# control_v1.net
KiCad netlist of a schematic drawn in EAGLE
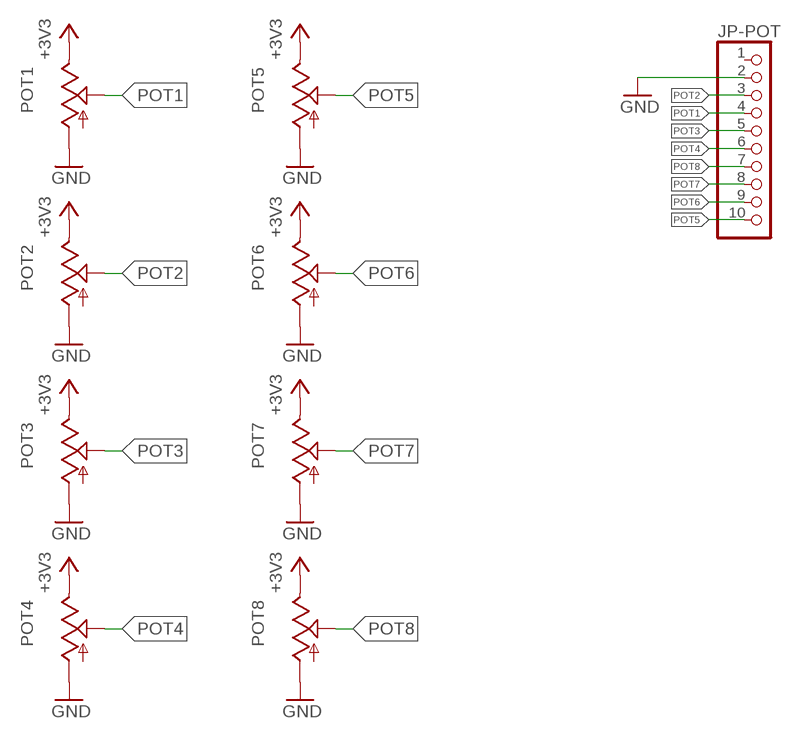
[diagram p0: schematic, sheet 1]
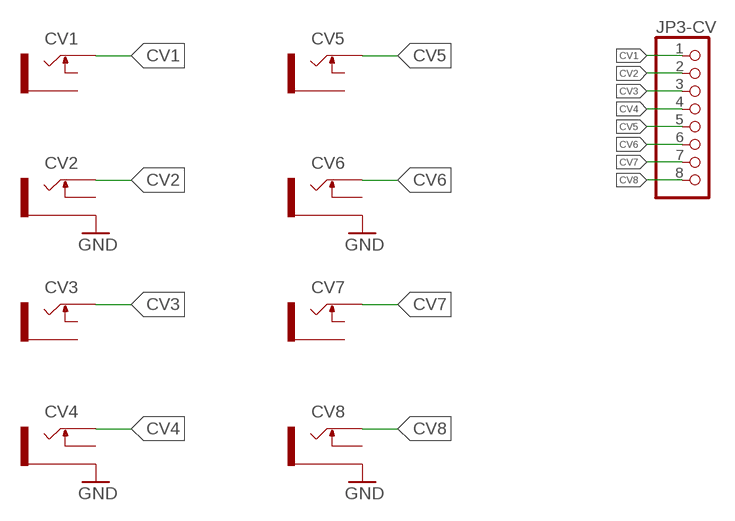
[diagram p1: schematic, sheet 2]
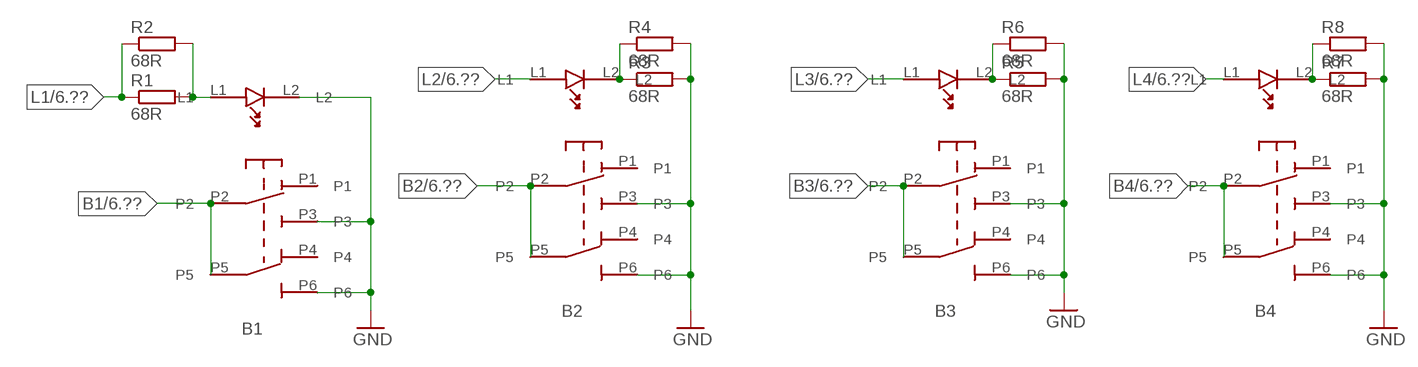
[diagram p2: schematic, sheet 3]
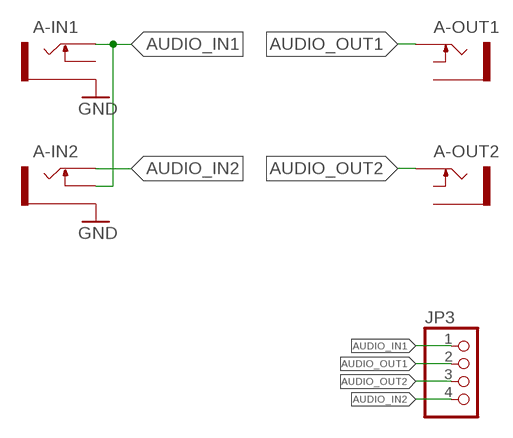
[diagram p3: schematic, sheet 4]
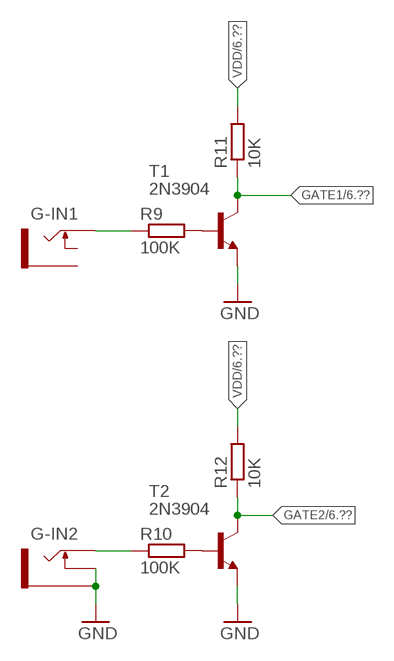
[diagram p4: schematic, sheet 5]
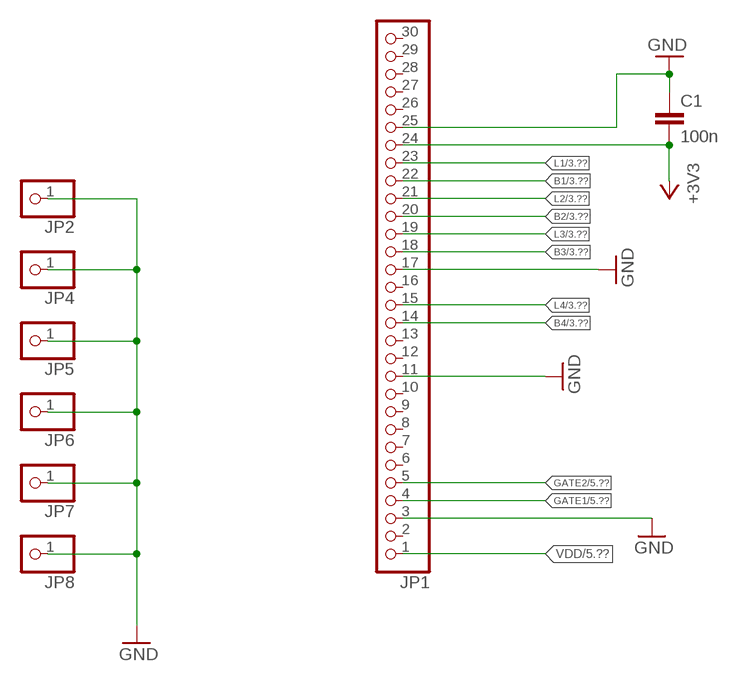
[diagram p5: schematic, sheet 6]

(export (version "E")
  (design (tool "Eeschema 10.0.6"))
  (components
    (comp (ref "JP-POT")
      (value "PINHD-1X10_2.54")
      (footprint "eagle-import:1X10")
      (libsource (lib "eagle-import") (part "PINHD-1X10_2.54"))
    )
    (comp (ref "POT1")
      (value "9MM_SNAP-IN_POT_")
      (footprint "eagle-import:9MM_SNAP-IN_POT")
      (libsource (lib "eagle-import") (part "9MM_SNAP-IN_POT_"))
    )
    (comp (ref "POT2")
      (value "9MM_SNAP-IN_POT_")
      (footprint "eagle-import:9MM_SNAP-IN_POT")
      (libsource (lib "eagle-import") (part "9MM_SNAP-IN_POT_"))
    )
    (comp (ref "POT3")
      (value "9MM_SNAP-IN_POT_")
      (footprint "eagle-import:9MM_SNAP-IN_POT")
      (libsource (lib "eagle-import") (part "9MM_SNAP-IN_POT_"))
    )
    (comp (ref "POT4")
      (value "9MM_SNAP-IN_POT_")
      (footprint "eagle-import:9MM_SNAP-IN_POT")
      (libsource (lib "eagle-import") (part "9MM_SNAP-IN_POT_"))
    )
    (comp (ref "POT5")
      (value "9MM_SNAP-IN_POT_")
      (footprint "eagle-import:9MM_SNAP-IN_POT")
      (libsource (lib "eagle-import") (part "9MM_SNAP-IN_POT_"))
    )
    (comp (ref "POT6")
      (value "9MM_SNAP-IN_POT_")
      (footprint "eagle-import:9MM_SNAP-IN_POT")
      (libsource (lib "eagle-import") (part "9MM_SNAP-IN_POT_"))
    )
    (comp (ref "POT7")
      (value "9MM_SNAP-IN_POT_")
      (footprint "eagle-import:9MM_SNAP-IN_POT")
      (libsource (lib "eagle-import") (part "9MM_SNAP-IN_POT_"))
    )
    (comp (ref "POT8")
      (value "9MM_SNAP-IN_POT_")
      (footprint "eagle-import:9MM_SNAP-IN_POT")
      (libsource (lib "eagle-import") (part "9MM_SNAP-IN_POT_"))
    )
    (comp (ref "C1")
      (value "100n")
      (footprint "eagle-import:C025-025X050")
      (libsource (lib "eagle-import") (part "C-EU025-025X050"))
    )
    (comp (ref "JP1")
      (value "PINHD-1X30")
      (footprint "eagle-import:1X30")
      (libsource (lib "eagle-import") (part "PINHD-1X30"))
    )
    (comp (ref "JP2")
      (value "PINHD-1X1")
      (footprint "eagle-import:1X01")
      (libsource (lib "eagle-import") (part "PINHD-1X1"))
    )
    (comp (ref "JP4")
      (value "PINHD-1X1")
      (footprint "eagle-import:1X01")
      (libsource (lib "eagle-import") (part "PINHD-1X1"))
    )
    (comp (ref "JP5")
      (value "PINHD-1X1")
      (footprint "eagle-import:1X01")
      (libsource (lib "eagle-import") (part "PINHD-1X1"))
    )
    (comp (ref "JP6")
      (value "PINHD-1X1")
      (footprint "eagle-import:1X01")
      (libsource (lib "eagle-import") (part "PINHD-1X1"))
    )
    (comp (ref "JP7")
      (value "PINHD-1X1")
      (footprint "eagle-import:1X01")
      (libsource (lib "eagle-import") (part "PINHD-1X1"))
    )
    (comp (ref "JP8")
      (value "PINHD-1X1")
      (footprint "eagle-import:1X01")
      (libsource (lib "eagle-import") (part "PINHD-1X1"))
    )
    (comp (ref "G-IN1")
      (value "THONKICONNNEW")
      (footprint "eagle-import:WQP-PJ301M-12_JACK")
      (libsource (lib "eagle-import") (part "MusicThingModular mod_THONKICONNNEW"))
    )
    (comp (ref "G-IN2")
      (value "THONKICONNNEW")
      (footprint "eagle-import:WQP-PJ301M-12_JACK")
      (libsource (lib "eagle-import") (part "THONKICONNNEW"))
    )
    (comp (ref "R9")
      (value "100K")
      (footprint "eagle-import:0207_7")
      (libsource (lib "eagle-import") (part "R-EU_0207/7"))
    )
    (comp (ref "R10")
      (value "100K")
      (footprint "eagle-import:0207_7")
      (libsource (lib "eagle-import") (part "R-EU_0207/7"))
    )
    (comp (ref "R11")
      (value "10K")
      (footprint "eagle-import:0207_7")
      (libsource (lib "eagle-import") (part "R-EU_0207/7"))
    )
    (comp (ref "R12")
      (value "10K")
      (footprint "eagle-import:0207_7")
      (libsource (lib "eagle-import") (part "R-EU_0207/7"))
    )
    (comp (ref "T1")
      (value "2N3904")
      (footprint "eagle-import:TO92")
      (libsource (lib "eagle-import") (part "2N3904"))
    )
    (comp (ref "T2")
      (value "2N3904")
      (footprint "eagle-import:TO92")
      (libsource (lib "eagle-import") (part "2N3904"))
    )
    (comp (ref "B1")
      (value "LP4OA1PBCTG")
      (footprint "eagle-import:LP4OA1PBCT")
      (libsource (lib "eagle-import") (part "LP4OA1PBCTG"))
    )
    (comp (ref "B2")
      (value "LP4OA1PBCTG")
      (footprint "eagle-import:LP4OA1PBCT")
      (libsource (lib "eagle-import") (part "LP4OA1PBCTG"))
    )
    (comp (ref "B3")
      (value "LP4OA1PBCTG")
      (footprint "eagle-import:LP4OA1PBCT")
      (libsource (lib "eagle-import") (part "LP4OA1PBCTG"))
    )
    (comp (ref "B4")
      (value "LP4OA1PBCTG")
      (footprint "eagle-import:LP4OA1PBCT")
      (libsource (lib "eagle-import") (part "LP4OA1PBCTG"))
    )
    (comp (ref "R1")
      (value "68R")
      (footprint "eagle-import:0207_7")
      (libsource (lib "eagle-import") (part "R-EU_0207/7"))
    )
    (comp (ref "R2")
      (value "68R")
      (footprint "eagle-import:0207_7")
      (libsource (lib "eagle-import") (part "R-EU_0207/7"))
    )
    (comp (ref "R3")
      (value "68R")
      (footprint "eagle-import:0207_7")
      (libsource (lib "eagle-import") (part "R-EU_0207/7"))
    )
    (comp (ref "R4")
      (value "68R")
      (footprint "eagle-import:0207_7")
      (libsource (lib "eagle-import") (part "R-EU_0207/7"))
    )
    (comp (ref "R5")
      (value "68R")
      (footprint "eagle-import:0207_7")
      (libsource (lib "eagle-import") (part "R-EU_0207/7"))
    )
    (comp (ref "R6")
      (value "68R")
      (footprint "eagle-import:0207_7")
      (libsource (lib "eagle-import") (part "R-EU_0207/7"))
    )
    (comp (ref "R7")
      (value "68R")
      (footprint "eagle-import:0207_7")
      (libsource (lib "eagle-import") (part "R-EU_0207/7"))
    )
    (comp (ref "R8")
      (value "68R")
      (footprint "eagle-import:0207_7")
      (libsource (lib "eagle-import") (part "R-EU_0207/7"))
    )
    (comp (ref "CV1")
      (value "THONKICONNNEW")
      (footprint "eagle-import:WQP-PJ301M-12_JACK")
      (libsource (lib "eagle-import") (part "MusicThingModular mod_THONKICONNNEW"))
    )
    (comp (ref "CV2")
      (value "THONKICONNNEW")
      (footprint "eagle-import:WQP-PJ301M-12_JACK")
      (libsource (lib "eagle-import") (part "THONKICONNNEW"))
    )
    (comp (ref "CV3")
      (value "THONKICONNNEW")
      (footprint "eagle-import:WQP-PJ301M-12_JACK")
      (libsource (lib "eagle-import") (part "MusicThingModular mod_THONKICONNNEW"))
    )
    (comp (ref "CV4")
      (value "THONKICONNNEW")
      (footprint "eagle-import:WQP-PJ301M-12_JACK")
      (libsource (lib "eagle-import") (part "THONKICONNNEW"))
    )
    (comp (ref "CV5")
      (value "THONKICONNNEW")
      (footprint "eagle-import:WQP-PJ301M-12_JACK")
      (libsource (lib "eagle-import") (part "MusicThingModular mod_THONKICONNNEW"))
    )
    (comp (ref "CV6")
      (value "THONKICONNNEW")
      (footprint "eagle-import:WQP-PJ301M-12_JACK")
      (libsource (lib "eagle-import") (part "THONKICONNNEW"))
    )
    (comp (ref "CV7")
      (value "THONKICONNNEW")
      (footprint "eagle-import:WQP-PJ301M-12_JACK")
      (libsource (lib "eagle-import") (part "MusicThingModular mod_THONKICONNNEW"))
    )
    (comp (ref "CV8")
      (value "THONKICONNNEW")
      (footprint "eagle-import:WQP-PJ301M-12_JACK")
      (libsource (lib "eagle-import") (part "THONKICONNNEW"))
    )
    (comp (ref "JP3-CV")
      (value "PINHD-1X8")
      (footprint "eagle-import:1X08")
      (libsource (lib "eagle-import") (part "PINHD-1X8"))
    )
    (comp (ref "A-IN1")
      (value "THONKICONNNEW")
      (footprint "eagle-import:WQP-PJ301M-12_JACK")
      (libsource (lib "eagle-import") (part "THONKICONNNEW"))
    )
    (comp (ref "A-IN2")
      (value "THONKICONNNEW")
      (footprint "eagle-import:WQP-PJ301M-12_JACK")
      (libsource (lib "eagle-import") (part "THONKICONNNEW"))
    )
    (comp (ref "A-OUT1")
      (value "THONKICONNNEW")
      (footprint "eagle-import:WQP-PJ301M-12_JACK")
      (libsource (lib "eagle-import") (part "MusicThingModular mod_THONKICONNNEW"))
    )
    (comp (ref "A-OUT2")
      (value "THONKICONNNEW")
      (footprint "eagle-import:WQP-PJ301M-12_JACK")
      (libsource (lib "eagle-import") (part "MusicThingModular mod_THONKICONNNEW"))
    )
    (comp (ref "JP3")
      (value "PINHD-1X4")
      (footprint "eagle-import:1X04")
      (libsource (lib "eagle-import") (part "PINHD-1X4"))
    )
  )
  (nets
    (net (code "1") (name "+3V3") (class "Default")
      (node (ref "C1") (pin "2") (pinfunction "2_2") (pintype "passive"))
      (node (ref "JP1") (pin "24") (pinfunction "24_24") (pintype "passive"))
      (node (ref "POT1") (pin "3") (pinfunction "E_3") (pintype "passive"))
      (node (ref "POT2") (pin "3") (pinfunction "E_3") (pintype "passive"))
      (node (ref "POT3") (pin "3") (pinfunction "E_3") (pintype "passive"))
      (node (ref "POT4") (pin "3") (pinfunction "E_3") (pintype "passive"))
      (node (ref "POT5") (pin "3") (pinfunction "E_3") (pintype "passive"))
      (node (ref "POT6") (pin "3") (pinfunction "E_3") (pintype "passive"))
      (node (ref "POT7") (pin "3") (pinfunction "E_3") (pintype "passive"))
      (node (ref "POT8") (pin "3") (pinfunction "E_3") (pintype "passive"))
    )
    (net (code "2") (name "AUDIO_IN1") (class "Default")
      (node (ref "A-IN1") (pin "P$1_TIP") (pinfunction "TIP_P$1_TIP") (pintype "passive"))
      (node (ref "A-IN2") (pin "P$2_SWITCH") (pinfunction "SWITCH_P$2_SWITCH") (pintype "passive"))
      (node (ref "JP3") (pin "1") (pinfunction "1_1") (pintype "passive"))
    )
    (net (code "3") (name "AUDIO_IN2") (class "Default")
      (node (ref "A-IN2") (pin "P$1_TIP") (pinfunction "TIP_P$1_TIP") (pintype "passive"))
      (node (ref "JP3") (pin "4") (pinfunction "4_4") (pintype "passive"))
    )
    (net (code "4") (name "AUDIO_OUT1") (class "Default")
      (node (ref "A-OUT1") (pin "P$1_TIP") (pinfunction "TIP_P$1_TIP") (pintype "passive"))
      (node (ref "JP3") (pin "2") (pinfunction "2_2") (pintype "passive"))
    )
    (net (code "5") (name "AUDIO_OUT2") (class "Default")
      (node (ref "A-OUT2") (pin "P$1_TIP") (pinfunction "TIP_P$1_TIP") (pintype "passive"))
      (node (ref "JP3") (pin "3") (pinfunction "3_3") (pintype "passive"))
    )
    (net (code "6") (name "B1") (class "Default")
      (node (ref "B1") (pin "P2") (pinfunction "P2_P2") (pintype "bidirectional"))
      (node (ref "B1") (pin "P5") (pinfunction "P5_P5") (pintype "bidirectional"))
      (node (ref "JP1") (pin "22") (pinfunction "22_22") (pintype "passive"))
    )
    (net (code "7") (name "B2") (class "Default")
      (node (ref "B2") (pin "P2") (pinfunction "P2_P2") (pintype "bidirectional"))
      (node (ref "B2") (pin "P5") (pinfunction "P5_P5") (pintype "bidirectional"))
      (node (ref "JP1") (pin "20") (pinfunction "20_20") (pintype "passive"))
    )
    (net (code "8") (name "B3") (class "Default")
      (node (ref "B3") (pin "P2") (pinfunction "P2_P2") (pintype "bidirectional"))
      (node (ref "B3") (pin "P5") (pinfunction "P5_P5") (pintype "bidirectional"))
      (node (ref "JP1") (pin "18") (pinfunction "18_18") (pintype "passive"))
    )
    (net (code "9") (name "B4") (class "Default")
      (node (ref "B4") (pin "P2") (pinfunction "P2_P2") (pintype "bidirectional"))
      (node (ref "B4") (pin "P5") (pinfunction "P5_P5") (pintype "bidirectional"))
      (node (ref "JP1") (pin "14") (pinfunction "14_14") (pintype "passive"))
    )
    (net (code "10") (name "CV1") (class "Default")
      (node (ref "CV1") (pin "P$1_TIP") (pinfunction "TIP_P$1_TIP") (pintype "passive"))
      (node (ref "JP3-CV") (pin "1") (pinfunction "1_1") (pintype "passive"))
    )
    (net (code "11") (name "CV2") (class "Default")
      (node (ref "CV2") (pin "P$1_TIP") (pinfunction "TIP_P$1_TIP") (pintype "passive"))
      (node (ref "JP3-CV") (pin "2") (pinfunction "2_2") (pintype "passive"))
    )
    (net (code "12") (name "CV3") (class "Default")
      (node (ref "CV3") (pin "P$1_TIP") (pinfunction "TIP_P$1_TIP") (pintype "passive"))
      (node (ref "JP3-CV") (pin "3") (pinfunction "3_3") (pintype "passive"))
    )
    (net (code "13") (name "CV4") (class "Default")
      (node (ref "CV4") (pin "P$1_TIP") (pinfunction "TIP_P$1_TIP") (pintype "passive"))
      (node (ref "JP3-CV") (pin "4") (pinfunction "4_4") (pintype "passive"))
    )
    (net (code "14") (name "CV5") (class "Default")
      (node (ref "CV5") (pin "P$1_TIP") (pinfunction "TIP_P$1_TIP") (pintype "passive"))
      (node (ref "JP3-CV") (pin "5") (pinfunction "5_5") (pintype "passive"))
    )
    (net (code "15") (name "CV6") (class "Default")
      (node (ref "CV6") (pin "P$1_TIP") (pinfunction "TIP_P$1_TIP") (pintype "passive"))
      (node (ref "JP3-CV") (pin "6") (pinfunction "6_6") (pintype "passive"))
    )
    (net (code "16") (name "CV7") (class "Default")
      (node (ref "CV7") (pin "P$1_TIP") (pinfunction "TIP_P$1_TIP") (pintype "passive"))
      (node (ref "JP3-CV") (pin "7") (pinfunction "7_7") (pintype "passive"))
    )
    (net (code "17") (name "CV8") (class "Default")
      (node (ref "CV8") (pin "P$1_TIP") (pinfunction "TIP_P$1_TIP") (pintype "passive"))
      (node (ref "JP3-CV") (pin "8") (pinfunction "8_8") (pintype "passive"))
    )
    (net (code "18") (name "GATE1") (class "Default")
      (node (ref "JP1") (pin "4") (pinfunction "4_4") (pintype "passive"))
      (node (ref "R11") (pin "1") (pinfunction "1_1") (pintype "passive"))
      (node (ref "T1") (pin "1") (pinfunction "C_1") (pintype "passive"))
    )
    (net (code "19") (name "GATE2") (class "Default")
      (node (ref "JP1") (pin "5") (pinfunction "5_5") (pintype "passive"))
      (node (ref "R12") (pin "1") (pinfunction "1_1") (pintype "passive"))
      (node (ref "T2") (pin "1") (pinfunction "C_1") (pintype "passive"))
    )
    (net (code "20") (name "GND") (class "Default")
      (node (ref "A-IN1") (pin "P$3_SLEEVE") (pinfunction "SLEEVE_P$3_SLEEVE") (pintype "passive"))
      (node (ref "A-IN2") (pin "P$3_SLEEVE") (pinfunction "SLEEVE_P$3_SLEEVE") (pintype "passive"))
      (node (ref "B1") (pin "L2") (pinfunction "L2_L2") (pintype "output"))
      (node (ref "B1") (pin "P3") (pinfunction "P3_P3") (pintype "bidirectional"))
      (node (ref "B1") (pin "P6") (pinfunction "P6_P6") (pintype "bidirectional"))
      (node (ref "B2") (pin "P3") (pinfunction "P3_P3") (pintype "bidirectional"))
      (node (ref "B2") (pin "P6") (pinfunction "P6_P6") (pintype "bidirectional"))
      (node (ref "B3") (pin "P3") (pinfunction "P3_P3") (pintype "bidirectional"))
      (node (ref "B3") (pin "P6") (pinfunction "P6_P6") (pintype "bidirectional"))
      (node (ref "B4") (pin "P3") (pinfunction "P3_P3") (pintype "bidirectional"))
      (node (ref "B4") (pin "P6") (pinfunction "P6_P6") (pintype "bidirectional"))
      (node (ref "C1") (pin "1") (pinfunction "1_1") (pintype "passive"))
      (node (ref "CV2") (pin "P$3_SLEEVE") (pinfunction "SLEEVE_P$3_SLEEVE") (pintype "passive"))
      (node (ref "CV4") (pin "P$3_SLEEVE") (pinfunction "SLEEVE_P$3_SLEEVE") (pintype "passive"))
      (node (ref "CV6") (pin "P$3_SLEEVE") (pinfunction "SLEEVE_P$3_SLEEVE") (pintype "passive"))
      (node (ref "CV8") (pin "P$3_SLEEVE") (pinfunction "SLEEVE_P$3_SLEEVE") (pintype "passive"))
      (node (ref "G-IN2") (pin "P$2_SWITCH") (pinfunction "SWITCH_P$2_SWITCH") (pintype "passive"))
      (node (ref "G-IN2") (pin "P$3_SLEEVE") (pinfunction "SLEEVE_P$3_SLEEVE") (pintype "passive"))
      (node (ref "JP-POT") (pin "2") (pinfunction "2_2") (pintype "passive"))
      (node (ref "JP1") (pin "11") (pinfunction "11_11") (pintype "passive"))
      (node (ref "JP1") (pin "17") (pinfunction "17_17") (pintype "passive"))
      (node (ref "JP1") (pin "25") (pinfunction "25_25") (pintype "passive"))
      (node (ref "JP1") (pin "3") (pinfunction "3_3") (pintype "passive"))
      (node (ref "JP2") (pin "1") (pinfunction "1_1") (pintype "passive"))
      (node (ref "JP4") (pin "1") (pinfunction "1_1") (pintype "passive"))
      (node (ref "JP5") (pin "1") (pinfunction "1_1") (pintype "passive"))
      (node (ref "JP6") (pin "1") (pinfunction "1_1") (pintype "passive"))
      (node (ref "JP7") (pin "1") (pinfunction "1_1") (pintype "passive"))
      (node (ref "JP8") (pin "1") (pinfunction "1_1") (pintype "passive"))
      (node (ref "POT1") (pin "1") (pinfunction "A_1") (pintype "passive"))
      (node (ref "POT2") (pin "1") (pinfunction "A_1") (pintype "passive"))
      (node (ref "POT3") (pin "1") (pinfunction "A_1") (pintype "passive"))
      (node (ref "POT4") (pin "1") (pinfunction "A_1") (pintype "passive"))
      (node (ref "POT5") (pin "1") (pinfunction "A_1") (pintype "passive"))
      (node (ref "POT6") (pin "1") (pinfunction "A_1") (pintype "passive"))
      (node (ref "POT7") (pin "1") (pinfunction "A_1") (pintype "passive"))
      (node (ref "POT8") (pin "1") (pinfunction "A_1") (pintype "passive"))
      (node (ref "R3") (pin "2") (pinfunction "2_2") (pintype "passive"))
      (node (ref "R4") (pin "2") (pinfunction "2_2") (pintype "passive"))
      (node (ref "R5") (pin "2") (pinfunction "2_2") (pintype "passive"))
      (node (ref "R6") (pin "2") (pinfunction "2_2") (pintype "passive"))
      (node (ref "R7") (pin "2") (pinfunction "2_2") (pintype "passive"))
      (node (ref "R8") (pin "2") (pinfunction "2_2") (pintype "passive"))
      (node (ref "T1") (pin "3") (pinfunction "E_3") (pintype "passive"))
      (node (ref "T2") (pin "3") (pinfunction "E_3") (pintype "passive"))
    )
    (net (code "21") (name "L1") (class "Default")
      (node (ref "JP1") (pin "23") (pinfunction "23_23") (pintype "passive"))
      (node (ref "R1") (pin "1") (pinfunction "1_1") (pintype "passive"))
      (node (ref "R2") (pin "1") (pinfunction "1_1") (pintype "passive"))
    )
    (net (code "22") (name "L2") (class "Default")
      (node (ref "B2") (pin "L1") (pinfunction "L1_L1") (pintype "input"))
      (node (ref "JP1") (pin "21") (pinfunction "21_21") (pintype "passive"))
    )
    (net (code "23") (name "L3") (class "Default")
      (node (ref "B3") (pin "L1") (pinfunction "L1_L1") (pintype "input"))
      (node (ref "JP1") (pin "19") (pinfunction "19_19") (pintype "passive"))
    )
    (net (code "24") (name "L4") (class "Default")
      (node (ref "B4") (pin "L1") (pinfunction "L1_L1") (pintype "input"))
      (node (ref "JP1") (pin "15") (pinfunction "15_15") (pintype "passive"))
    )
    (net (code "25") (name "Net-(B1-PadL1)") (class "Default")
      (node (ref "B1") (pin "L1") (pinfunction "L1_L1") (pintype "input"))
      (node (ref "R1") (pin "2") (pinfunction "2_2") (pintype "passive"))
      (node (ref "R2") (pin "2") (pinfunction "2_2") (pintype "passive"))
    )
    (net (code "26") (name "Net-(B2-PadL2)") (class "Default")
      (node (ref "B2") (pin "L2") (pinfunction "L2_L2") (pintype "output"))
      (node (ref "R3") (pin "1") (pinfunction "1_1") (pintype "passive"))
      (node (ref "R4") (pin "1") (pinfunction "1_1") (pintype "passive"))
    )
    (net (code "27") (name "Net-(B3-PadL2)") (class "Default")
      (node (ref "B3") (pin "L2") (pinfunction "L2_L2") (pintype "output"))
      (node (ref "R5") (pin "1") (pinfunction "1_1") (pintype "passive"))
      (node (ref "R6") (pin "1") (pinfunction "1_1") (pintype "passive"))
    )
    (net (code "28") (name "Net-(B4-PadL2)") (class "Default")
      (node (ref "B4") (pin "L2") (pinfunction "L2_L2") (pintype "output"))
      (node (ref "R7") (pin "1") (pinfunction "1_1") (pintype "passive"))
      (node (ref "R8") (pin "1") (pinfunction "1_1") (pintype "passive"))
    )
    (net (code "29") (name "Net-(G-IN1-TIP)") (class "Default")
      (node (ref "G-IN1") (pin "P$1_TIP") (pinfunction "TIP_P$1_TIP") (pintype "passive"))
      (node (ref "R9") (pin "1") (pinfunction "1_1") (pintype "passive"))
    )
    (net (code "30") (name "Net-(G-IN2-TIP)") (class "Default")
      (node (ref "G-IN2") (pin "P$1_TIP") (pinfunction "TIP_P$1_TIP") (pintype "passive"))
      (node (ref "R10") (pin "1") (pinfunction "1_1") (pintype "passive"))
    )
    (net (code "31") (name "Net-(T1-B)") (class "Default")
      (node (ref "R9") (pin "2") (pinfunction "2_2") (pintype "passive"))
      (node (ref "T1") (pin "2") (pinfunction "B_2") (pintype "passive"))
    )
    (net (code "32") (name "Net-(T2-B)") (class "Default")
      (node (ref "R10") (pin "2") (pinfunction "2_2") (pintype "passive"))
      (node (ref "T2") (pin "2") (pinfunction "B_2") (pintype "passive"))
    )
    (net (code "33") (name "POT1") (class "Default")
      (node (ref "JP-POT") (pin "4") (pinfunction "4_4") (pintype "passive"))
      (node (ref "POT1") (pin "2") (pinfunction "S_2") (pintype "passive"))
    )
    (net (code "34") (name "POT2") (class "Default")
      (node (ref "JP-POT") (pin "3") (pinfunction "3_3") (pintype "passive"))
      (node (ref "POT2") (pin "2") (pinfunction "S_2") (pintype "passive"))
    )
    (net (code "35") (name "POT3") (class "Default")
      (node (ref "JP-POT") (pin "5") (pinfunction "5_5") (pintype "passive"))
      (node (ref "POT3") (pin "2") (pinfunction "S_2") (pintype "passive"))
    )
    (net (code "36") (name "POT4") (class "Default")
      (node (ref "JP-POT") (pin "6") (pinfunction "6_6") (pintype "passive"))
      (node (ref "POT4") (pin "2") (pinfunction "S_2") (pintype "passive"))
    )
    (net (code "37") (name "POT5") (class "Default")
      (node (ref "JP-POT") (pin "10") (pinfunction "10_10") (pintype "passive"))
      (node (ref "POT5") (pin "2") (pinfunction "S_2") (pintype "passive"))
    )
    (net (code "38") (name "POT6") (class "Default")
      (node (ref "JP-POT") (pin "9") (pinfunction "9_9") (pintype "passive"))
      (node (ref "POT6") (pin "2") (pinfunction "S_2") (pintype "passive"))
    )
    (net (code "39") (name "POT7") (class "Default")
      (node (ref "JP-POT") (pin "8") (pinfunction "8_8") (pintype "passive"))
      (node (ref "POT7") (pin "2") (pinfunction "S_2") (pintype "passive"))
    )
    (net (code "40") (name "POT8") (class "Default")
      (node (ref "JP-POT") (pin "7") (pinfunction "7_7") (pintype "passive"))
      (node (ref "POT8") (pin "2") (pinfunction "S_2") (pintype "passive"))
    )
    (net (code "41") (name "VDD") (class "Default")
      (node (ref "JP1") (pin "1") (pinfunction "1_1") (pintype "passive"))
      (node (ref "R11") (pin "2") (pinfunction "2_2") (pintype "passive"))
      (node (ref "R12") (pin "2") (pinfunction "2_2") (pintype "passive"))
    )
    (net (code "42") (name "unconnected-(A-IN1-SWITCH-PadP$2_SWITCH)") (class "Default")
      (node (ref "A-IN1") (pin "P$2_SWITCH") (pinfunction "SWITCH_P$2_SWITCH") (pintype "passive"))
    )
    (net (code "43") (name "unconnected-(B1-PadP1)") (class "Default")
      (node (ref "B1") (pin "P1") (pinfunction "P1_P1") (pintype "bidirectional"))
    )
    (net (code "44") (name "unconnected-(B1-PadP4)") (class "Default")
      (node (ref "B1") (pin "P4") (pinfunction "P4_P4") (pintype "bidirectional"))
    )
    (net (code "45") (name "unconnected-(B2-PadP1)") (class "Default")
      (node (ref "B2") (pin "P1") (pinfunction "P1_P1") (pintype "bidirectional"))
    )
    (net (code "46") (name "unconnected-(B2-PadP4)") (class "Default")
      (node (ref "B2") (pin "P4") (pinfunction "P4_P4") (pintype "bidirectional"))
    )
    (net (code "47") (name "unconnected-(B3-PadP1)") (class "Default")
      (node (ref "B3") (pin "P1") (pinfunction "P1_P1") (pintype "bidirectional"))
    )
    (net (code "48") (name "unconnected-(B3-PadP4)") (class "Default")
      (node (ref "B3") (pin "P4") (pinfunction "P4_P4") (pintype "bidirectional"))
    )
    (net (code "49") (name "unconnected-(B4-PadP1)") (class "Default")
      (node (ref "B4") (pin "P1") (pinfunction "P1_P1") (pintype "bidirectional"))
    )
    (net (code "50") (name "unconnected-(B4-PadP4)") (class "Default")
      (node (ref "B4") (pin "P4") (pinfunction "P4_P4") (pintype "bidirectional"))
    )
    (net (code "51") (name "unconnected-(CV2-SWITCH-PadP$2_SWITCH)") (class "Default")
      (node (ref "CV2") (pin "P$2_SWITCH") (pinfunction "SWITCH_P$2_SWITCH") (pintype "passive"))
    )
    (net (code "52") (name "unconnected-(CV4-SWITCH-PadP$2_SWITCH)") (class "Default")
      (node (ref "CV4") (pin "P$2_SWITCH") (pinfunction "SWITCH_P$2_SWITCH") (pintype "passive"))
    )
    (net (code "53") (name "unconnected-(CV6-SWITCH-PadP$2_SWITCH)") (class "Default")
      (node (ref "CV6") (pin "P$2_SWITCH") (pinfunction "SWITCH_P$2_SWITCH") (pintype "passive"))
    )
    (net (code "54") (name "unconnected-(CV8-SWITCH-PadP$2_SWITCH)") (class "Default")
      (node (ref "CV8") (pin "P$2_SWITCH") (pinfunction "SWITCH_P$2_SWITCH") (pintype "passive"))
    )
    (net (code "55") (name "unconnected-(JP-POT-Pad1)") (class "Default")
      (node (ref "JP-POT") (pin "1") (pinfunction "1_1") (pintype "passive"))
    )
    (net (code "56") (name "unconnected-(JP1-Pad2)") (class "Default")
      (node (ref "JP1") (pin "2") (pinfunction "2_2") (pintype "passive"))
    )
    (net (code "57") (name "unconnected-(JP1-Pad6)") (class "Default")
      (node (ref "JP1") (pin "6") (pinfunction "6_6") (pintype "passive"))
    )
    (net (code "58") (name "unconnected-(JP1-Pad7)") (class "Default")
      (node (ref "JP1") (pin "7") (pinfunction "7_7") (pintype "passive"))
    )
    (net (code "59") (name "unconnected-(JP1-Pad8)") (class "Default")
      (node (ref "JP1") (pin "8") (pinfunction "8_8") (pintype "passive"))
    )
    (net (code "60") (name "unconnected-(JP1-Pad9)") (class "Default")
      (node (ref "JP1") (pin "9") (pinfunction "9_9") (pintype "passive"))
    )
    (net (code "61") (name "unconnected-(JP1-Pad10)") (class "Default")
      (node (ref "JP1") (pin "10") (pinfunction "10_10") (pintype "passive"))
    )
    (net (code "62") (name "unconnected-(JP1-Pad12)") (class "Default")
      (node (ref "JP1") (pin "12") (pinfunction "12_12") (pintype "passive"))
    )
    (net (code "63") (name "unconnected-(JP1-Pad13)") (class "Default")
      (node (ref "JP1") (pin "13") (pinfunction "13_13") (pintype "passive"))
    )
    (net (code "64") (name "unconnected-(JP1-Pad16)") (class "Default")
      (node (ref "JP1") (pin "16") (pinfunction "16_16") (pintype "passive"))
    )
    (net (code "65") (name "unconnected-(JP1-Pad26)") (class "Default")
      (node (ref "JP1") (pin "26") (pinfunction "26_26") (pintype "passive"))
    )
    (net (code "66") (name "unconnected-(JP1-Pad27)") (class "Default")
      (node (ref "JP1") (pin "27") (pinfunction "27_27") (pintype "passive"))
    )
    (net (code "67") (name "unconnected-(JP1-Pad28)") (class "Default")
      (node (ref "JP1") (pin "28") (pinfunction "28_28") (pintype "passive"))
    )
    (net (code "68") (name "unconnected-(JP1-Pad29)") (class "Default")
      (node (ref "JP1") (pin "29") (pinfunction "29_29") (pintype "passive"))
    )
    (net (code "69") (name "unconnected-(JP1-Pad30)") (class "Default")
      (node (ref "JP1") (pin "30") (pinfunction "30_30") (pintype "passive"))
    )
  )
)
